# usbkey.net
KiCad netlist of a schematic drawn in EAGLE
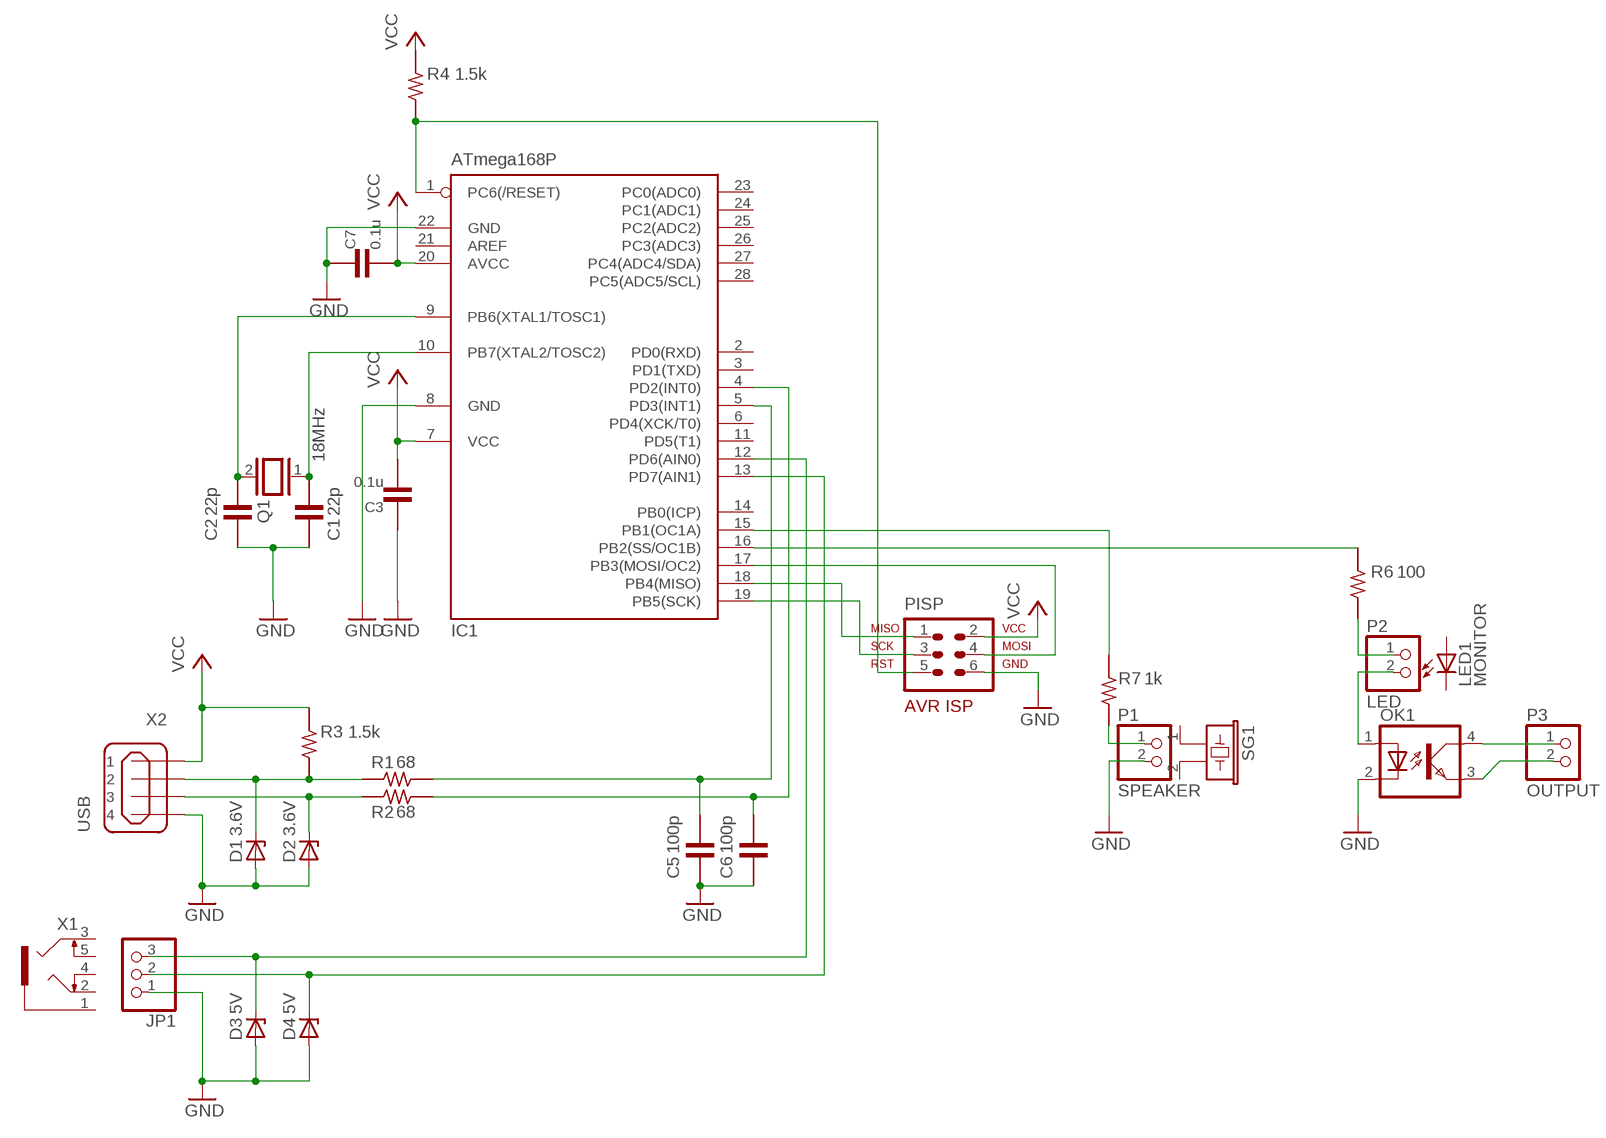
[diagram p0: schematic, sheet 1]

(export (version "E")
  (design (tool "Eeschema 10.0.6"))
  (components
    (comp (ref "C1")
      (value "22p")
      (footprint "eagle-import:50-0302-2.54")
      (libsource (lib "eagle-import") (part "C-50V-0302-2.54"))
    )
    (comp (ref "C2")
      (value "22p")
      (footprint "eagle-import:50-0302-2.54")
      (libsource (lib "eagle-import") (part "C-50V-0302-2.54"))
    )
    (comp (ref "C3")
      (value "0.1u")
      (footprint "eagle-import:50-0302-2.54")
      (libsource (lib "eagle-import") (part "C-50V-0302-2.54"))
    )
    (comp (ref "C5")
      (value "100p")
      (footprint "eagle-import:50-0302-2.54")
      (libsource (lib "eagle-import") (part "C-50V-0302-2.54"))
    )
    (comp (ref "C6")
      (value "100p")
      (footprint "eagle-import:50-0302-2.54")
      (libsource (lib "eagle-import") (part "C-50V-0302-2.54"))
    )
    (comp (ref "C7")
      (value "0.1u")
      (footprint "eagle-import:50-0302-2.54")
      (libsource (lib "eagle-import") (part "C-50V-0302-2.54"))
    )
    (comp (ref "D1")
      (value "3.6V")
      (footprint "eagle-import:DO35Z10")
      (libsource (lib "eagle-import") (part "BZX55"))
    )
    (comp (ref "D2")
      (value "3.6V")
      (footprint "eagle-import:DO35Z10")
      (libsource (lib "eagle-import") (part "BZX55"))
    )
    (comp (ref "D3")
      (value "5V")
      (footprint "eagle-import:DO35Z10")
      (libsource (lib "eagle-import") (part "BZX55"))
    )
    (comp (ref "D4")
      (value "5V")
      (footprint "eagle-import:DO35Z10")
      (libsource (lib "eagle-import") (part "BZX55"))
    )
    (comp (ref "IC1")
      (value "ATmega168P")
      (footprint "eagle-import:DIL28-3")
      (libsource (lib "eagle-import") (part "MEGA8-P"))
    )
    (comp (ref "JP1")
      (value "PINHD-1X3")
      (footprint "eagle-import:1X03")
      (libsource (lib "eagle-import") (part "PINHD-1X3"))
    )
    (comp (ref "LED1")
      (value "MONITOR")
      (footprint "eagle-import:LED3MM")
      (libsource (lib "eagle-import") (part "LED3MM"))
    )
    (comp (ref "OK1")
      (value "LTV816")
      (footprint "eagle-import:DIL04")
      (libsource (lib "eagle-import") (part "LTV816"))
    )
    (comp (ref "P1")
      (value "SPEAKER")
      (footprint "eagle-import:1X02")
      (libsource (lib "eagle-import") (part "PINHD-1X2"))
    )
    (comp (ref "P2")
      (value "LED")
      (footprint "eagle-import:1X02")
      (libsource (lib "eagle-import") (part "PINHD-1X2"))
    )
    (comp (ref "P3")
      (value "OUTPUT")
      (footprint "eagle-import:1X02")
      (libsource (lib "eagle-import") (part "PINHD-1X2"))
    )
    (comp (ref "PISP")
      (value "AVR-ISP-6VERT")
      (footprint "eagle-import:AVR-ISP-6")
      (libsource (lib "eagle-import") (part "AVR-ISP-6VERT"))
    )
    (comp (ref "Q1")
      (value "18MHz")
      (footprint "eagle-import:QS")
      (libsource (lib "eagle-import") (part "XTAL/S"))
    )
    (comp (ref "R1")
      (value "68")
      (footprint "eagle-import:1_4W-2.54V")
      (libsource (lib "eagle-import") (part "R-1/4W-02.54-V"))
    )
    (comp (ref "R2")
      (value "68")
      (footprint "eagle-import:1_4W-2.54V")
      (libsource (lib "eagle-import") (part "R-1/4W-02.54-V"))
    )
    (comp (ref "R3")
      (value "1.5k")
      (footprint "eagle-import:1_4W-7.62H")
      (libsource (lib "eagle-import") (part "R-1/4W-07.62"))
    )
    (comp (ref "R4")
      (value "1.5k")
      (footprint "eagle-import:1_4W-2.54V")
      (libsource (lib "eagle-import") (part "R-1/4W-02.54-V"))
    )
    (comp (ref "R6")
      (value "100")
      (footprint "eagle-import:1_4W-7.62H")
      (libsource (lib "eagle-import") (part "R-1/4W-07.62"))
    )
    (comp (ref "R7")
      (value "1k")
      (footprint "eagle-import:1_4W-7.62H")
      (libsource (lib "eagle-import") (part "R-1/4W-07.62"))
    )
    (comp (ref "SG1")
      (value "EFBRD22C41")
      (footprint "eagle-import:EFBRD22C41")
      (libsource (lib "eagle-import") (part "EFB?RD22C41"))
    )
    (comp (ref "X1")
      (value "1503_09")
      (footprint "eagle-import:1503_09")
      (libsource (lib "eagle-import") (part "1503_09"))
    )
    (comp (ref "X2")
      (value "USB")
      (footprint "eagle-import:85-32004-10X")
      (libsource (lib "eagle-import") (part "MINI-USB_SHIELD4P-85-32004-10X"))
    )
  )
  (nets
    (net (code "1") (name "GND") (class "Default")
      (node (ref "C1") (pin "PAD2") (pinfunction "2_PAD2") (pintype "passive"))
      (node (ref "C2") (pin "PAD2") (pinfunction "2_PAD2") (pintype "passive"))
      (node (ref "C3") (pin "PAD1") (pinfunction "1_PAD1") (pintype "passive"))
      (node (ref "C5") (pin "PAD2") (pinfunction "2_PAD2") (pintype "passive"))
      (node (ref "C6") (pin "PAD2") (pinfunction "2_PAD2") (pintype "passive"))
      (node (ref "C7") (pin "PAD1") (pinfunction "1_PAD1") (pintype "passive"))
      (node (ref "D1") (pin "A") (pinfunction "A_A") (pintype "passive"))
      (node (ref "D2") (pin "A") (pinfunction "A_A") (pintype "passive"))
      (node (ref "D3") (pin "A") (pinfunction "A_A") (pintype "passive"))
      (node (ref "D4") (pin "A") (pinfunction "A_A") (pintype "passive"))
      (node (ref "IC1") (pin "22") (pinfunction "GND_22") (pintype "power_in"))
      (node (ref "IC1") (pin "8") (pinfunction "GND_8") (pintype "power_in"))
      (node (ref "JP1") (pin "1") (pinfunction "1_1") (pintype "passive"))
      (node (ref "OK1") (pin "2") (pinfunction "C_2") (pintype "passive"))
      (node (ref "P1") (pin "2") (pinfunction "2_2") (pintype "passive"))
      (node (ref "PISP") (pin "6") (pinfunction "6_6") (pintype "passive"))
      (node (ref "X2") (pin "4") (pinfunction "4_4") (pintype "passive"))
    )
    (net (code "2") (name "Net-(C1-1)") (class "Default")
      (node (ref "C1") (pin "PAD1") (pinfunction "1_PAD1") (pintype "passive"))
      (node (ref "IC1") (pin "10") (pinfunction "PB7(XTAL2/TOSC2)_10") (pintype "bidirectional"))
      (node (ref "Q1") (pin "1") (pinfunction "1_1") (pintype "passive"))
    )
    (net (code "3") (name "Net-(C2-1)") (class "Default")
      (node (ref "C2") (pin "PAD1") (pinfunction "1_PAD1") (pintype "passive"))
      (node (ref "IC1") (pin "9") (pinfunction "PB6(XTAL1/TOSC1)_9") (pintype "bidirectional"))
      (node (ref "Q1") (pin "2") (pinfunction "2_2") (pintype "passive"))
    )
    (net (code "4") (name "Net-(C5-1)") (class "Default")
      (node (ref "C5") (pin "PAD1") (pinfunction "1_PAD1") (pintype "passive"))
      (node (ref "IC1") (pin "5") (pinfunction "PD3(INT1)_5") (pintype "bidirectional"))
      (node (ref "R1") (pin "PAD2") (pinfunction "2_PAD2") (pintype "passive"))
    )
    (net (code "5") (name "Net-(C6-1)") (class "Default")
      (node (ref "C6") (pin "PAD1") (pinfunction "1_PAD1") (pintype "passive"))
      (node (ref "IC1") (pin "4") (pinfunction "PD2(INT0)_4") (pintype "bidirectional"))
      (node (ref "R2") (pin "PAD2") (pinfunction "2_PAD2") (pintype "passive"))
    )
    (net (code "6") (name "Net-(IC1-PB1(OC1A))") (class "Default")
      (node (ref "IC1") (pin "15") (pinfunction "PB1(OC1A)_15") (pintype "bidirectional"))
      (node (ref "R7") (pin "PAD2") (pinfunction "2_PAD2") (pintype "passive"))
    )
    (net (code "7") (name "Net-(IC1-PB2(SS{slash}OC1B))") (class "Default")
      (node (ref "IC1") (pin "16") (pinfunction "PB2(SS/OC1B)_16") (pintype "bidirectional"))
      (node (ref "R6") (pin "PAD2") (pinfunction "2_PAD2") (pintype "passive"))
    )
    (net (code "8") (name "Net-(IC1-PB3(MOSI{slash}OC2))") (class "Default")
      (node (ref "IC1") (pin "17") (pinfunction "PB3(MOSI/OC2)_17") (pintype "bidirectional"))
      (node (ref "PISP") (pin "4") (pinfunction "4_4") (pintype "passive"))
    )
    (net (code "9") (name "Net-(IC1-PB4(MISO))") (class "Default")
      (node (ref "IC1") (pin "18") (pinfunction "PB4(MISO)_18") (pintype "bidirectional"))
      (node (ref "PISP") (pin "1") (pinfunction "1_1") (pintype "passive"))
    )
    (net (code "10") (name "Net-(IC1-PB5(SCK))") (class "Default")
      (node (ref "IC1") (pin "19") (pinfunction "PB5(SCK)_19") (pintype "bidirectional"))
      (node (ref "PISP") (pin "3") (pinfunction "3_3") (pintype "passive"))
    )
    (net (code "11") (name "Net-(IC1-PC6({slash}RESET))") (class "Default")
      (node (ref "IC1") (pin "1") (pinfunction "PC6(/RESET)_1") (pintype "bidirectional"))
      (node (ref "PISP") (pin "5") (pinfunction "5_5") (pintype "passive"))
      (node (ref "R4") (pin "PAD1") (pinfunction "1_PAD1") (pintype "passive"))
    )
    (net (code "12") (name "Net-(IC1-PD6(AIN0))") (class "Default")
      (node (ref "D3") (pin "C") (pinfunction "C_C") (pintype "passive"))
      (node (ref "IC1") (pin "12") (pinfunction "PD6(AIN0)_12") (pintype "bidirectional"))
      (node (ref "JP1") (pin "3") (pinfunction "3_3") (pintype "passive"))
    )
    (net (code "13") (name "Net-(IC1-PD7(AIN1))") (class "Default")
      (node (ref "D4") (pin "C") (pinfunction "C_C") (pintype "passive"))
      (node (ref "IC1") (pin "13") (pinfunction "PD7(AIN1)_13") (pintype "bidirectional"))
      (node (ref "JP1") (pin "2") (pinfunction "2_2") (pintype "passive"))
    )
    (net (code "14") (name "Net-(OK1-A)") (class "Default")
      (node (ref "OK1") (pin "1") (pinfunction "A_1") (pintype "passive"))
      (node (ref "P2") (pin "2") (pinfunction "2_2") (pintype "passive"))
    )
    (net (code "15") (name "Net-(OK1-COL)") (class "Default")
      (node (ref "OK1") (pin "4") (pinfunction "COL_4") (pintype "passive"))
      (node (ref "P3") (pin "1") (pinfunction "1_1") (pintype "passive"))
    )
    (net (code "16") (name "Net-(OK1-EMIT)") (class "Default")
      (node (ref "OK1") (pin "3") (pinfunction "EMIT_3") (pintype "passive"))
      (node (ref "P3") (pin "2") (pinfunction "2_2") (pintype "passive"))
    )
    (net (code "17") (name "Net-(R1-1)") (class "Default")
      (node (ref "D1") (pin "C") (pinfunction "C_C") (pintype "passive"))
      (node (ref "R1") (pin "PAD1") (pinfunction "1_PAD1") (pintype "passive"))
      (node (ref "R3") (pin "PAD1") (pinfunction "1_PAD1") (pintype "passive"))
      (node (ref "X2") (pin "2") (pinfunction "2_2") (pintype "passive"))
    )
    (net (code "18") (name "Net-(R2-1)") (class "Default")
      (node (ref "D2") (pin "C") (pinfunction "C_C") (pintype "passive"))
      (node (ref "R2") (pin "PAD1") (pinfunction "1_PAD1") (pintype "passive"))
      (node (ref "X2") (pin "3") (pinfunction "3_3") (pintype "passive"))
    )
    (net (code "19") (name "Net-(R6-1)") (class "Default")
      (node (ref "P2") (pin "1") (pinfunction "1_1") (pintype "passive"))
      (node (ref "R6") (pin "PAD1") (pinfunction "1_PAD1") (pintype "passive"))
    )
    (net (code "20") (name "Net-(R7-1)") (class "Default")
      (node (ref "P1") (pin "1") (pinfunction "1_1") (pintype "passive"))
      (node (ref "R7") (pin "PAD1") (pinfunction "1_PAD1") (pintype "passive"))
    )
    (net (code "21") (name "VCC") (class "Default")
      (node (ref "C3") (pin "PAD2") (pinfunction "2_PAD2") (pintype "passive"))
      (node (ref "C7") (pin "PAD2") (pinfunction "2_PAD2") (pintype "passive"))
      (node (ref "IC1") (pin "20") (pinfunction "AVCC_20") (pintype "power_in"))
      (node (ref "IC1") (pin "7") (pinfunction "VCC_7") (pintype "power_in"))
      (node (ref "PISP") (pin "2") (pinfunction "2_2") (pintype "passive"))
      (node (ref "R3") (pin "PAD2") (pinfunction "2_PAD2") (pintype "passive"))
      (node (ref "R4") (pin "PAD2") (pinfunction "2_PAD2") (pintype "passive"))
      (node (ref "X2") (pin "1") (pinfunction "1_1") (pintype "passive"))
    )
    (net (code "22") (name "unconnected-(IC1-AREF-Pad21)") (class "Default")
      (node (ref "IC1") (pin "21") (pinfunction "AREF_21") (pintype "passive"))
    )
    (net (code "23") (name "unconnected-(IC1-PB0(ICP)-Pad14)") (class "Default")
      (node (ref "IC1") (pin "14") (pinfunction "PB0(ICP)_14") (pintype "bidirectional"))
    )
    (net (code "24") (name "unconnected-(IC1-PC0(ADC0)-Pad23)") (class "Default")
      (node (ref "IC1") (pin "23") (pinfunction "PC0(ADC0)_23") (pintype "bidirectional"))
    )
    (net (code "25") (name "unconnected-(IC1-PC1(ADC1)-Pad24)") (class "Default")
      (node (ref "IC1") (pin "24") (pinfunction "PC1(ADC1)_24") (pintype "bidirectional"))
    )
    (net (code "26") (name "unconnected-(IC1-PC2(ADC2)-Pad25)") (class "Default")
      (node (ref "IC1") (pin "25") (pinfunction "PC2(ADC2)_25") (pintype "bidirectional"))
    )
    (net (code "27") (name "unconnected-(IC1-PC3(ADC3)-Pad26)") (class "Default")
      (node (ref "IC1") (pin "26") (pinfunction "PC3(ADC3)_26") (pintype "bidirectional"))
    )
    (net (code "28") (name "unconnected-(IC1-PC4(ADC4{slash}SDA)-Pad27)") (class "Default")
      (node (ref "IC1") (pin "27") (pinfunction "PC4(ADC4/SDA)_27") (pintype "bidirectional"))
    )
    (net (code "29") (name "unconnected-(IC1-PC5(ADC5{slash}SCL)-Pad28)") (class "Default")
      (node (ref "IC1") (pin "28") (pinfunction "PC5(ADC5/SCL)_28") (pintype "bidirectional"))
    )
    (net (code "30") (name "unconnected-(IC1-PD0(RXD)-Pad2)") (class "Default")
      (node (ref "IC1") (pin "2") (pinfunction "PD0(RXD)_2") (pintype "bidirectional"))
    )
    (net (code "31") (name "unconnected-(IC1-PD1(TXD)-Pad3)") (class "Default")
      (node (ref "IC1") (pin "3") (pinfunction "PD1(TXD)_3") (pintype "bidirectional"))
    )
    (net (code "32") (name "unconnected-(IC1-PD4(XCK{slash}T0)-Pad6)") (class "Default")
      (node (ref "IC1") (pin "6") (pinfunction "PD4(XCK/T0)_6") (pintype "bidirectional"))
    )
    (net (code "33") (name "unconnected-(IC1-PD5(T1)-Pad11)") (class "Default")
      (node (ref "IC1") (pin "11") (pinfunction "PD5(T1)_11") (pintype "bidirectional"))
    )
    (net (code "34") (name "unconnected-(LED1-C-PadK)") (class "Default")
      (node (ref "LED1") (pin "K") (pinfunction "C_K") (pintype "passive"))
    )
    (net (code "35") (name "unconnected-(LED1-PadA)") (class "Default")
      (node (ref "LED1") (pin "A") (pinfunction "A_A") (pintype "passive"))
    )
    (net (code "36") (name "unconnected-(SG1-Pad1)") (class "Default")
      (node (ref "SG1") (pin "1") (pinfunction "1_1") (pintype "passive"))
    )
    (net (code "37") (name "unconnected-(SG1-Pad2)") (class "Default")
      (node (ref "SG1") (pin "2") (pinfunction "2_2") (pintype "passive"))
    )
    (net (code "38") (name "unconnected-(X1-Pad1)") (class "Default")
      (node (ref "X1") (pin "1") (pinfunction "1_1") (pintype "passive"))
    )
    (net (code "39") (name "unconnected-(X1-Pad2)") (class "Default")
      (node (ref "X1") (pin "2") (pinfunction "2_2") (pintype "passive"))
    )
    (net (code "40") (name "unconnected-(X1-Pad3)") (class "Default")
      (node (ref "X1") (pin "3") (pinfunction "3_3") (pintype "passive"))
    )
    (net (code "41") (name "unconnected-(X1-Pad4)") (class "Default")
      (node (ref "X1") (pin "4") (pinfunction "4_4") (pintype "passive"))
    )
    (net (code "42") (name "unconnected-(X1-Pad5)") (class "Default")
      (node (ref "X1") (pin "5") (pinfunction "5_5") (pintype "passive"))
    )
  )
)
